# JLC_18V_ESB.net
KiCad netlist of a schematic drawn in Altium Designer
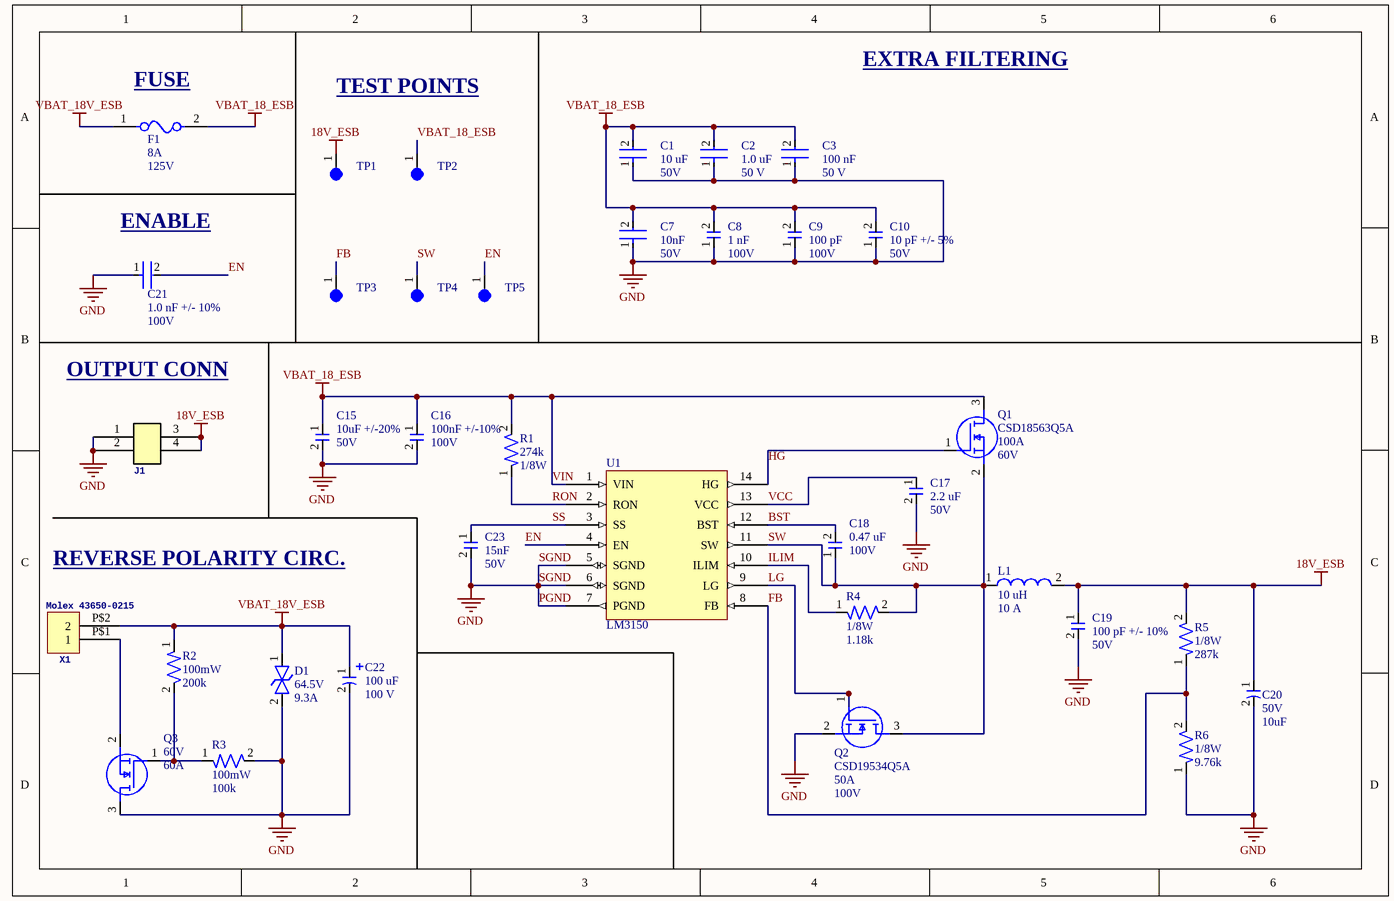
[diagram p0: JLC_18V_ESB.SchDoc]

(export (version "E")
  (design (tool "Eeschema 10.0.6"))
  (components
    (comp (ref "C1")
      (value "CL32B106KBJNNNE")
      (footprint "MasterLib:CAP-1210")
      (description "CAP CER 10UF 50V X7R 1210")
      (fields (field (name "VOLTAGE") "50V") (field (name "CAPACITANCE") "10 uF"))
      (libsource (lib "JLC_25") (part "CAP-10U-0002"))
    )
    (comp (ref "C2")
      (value "CC0805KKX7R9BB105")
      (footprint "MasterLib:CAP-0805")
      (description "CAP CER 1UF 50V X7R 0805")
      (fields (field (name "VOLTAGE") "50 V") (field (name "CAPACITANCE") "1.0 uF"))
      (libsource (lib "JLC_25") (part "CAP-1U-0001"))
    )
    (comp (ref "C3")
      (value "CC0805KRX7R9BB104")
      (footprint "MasterLib:CAP-0805")
      (description "CAP CER 0.1UF 50V X7R 0805")
      (fields (field (name "VOLTAGE RATING") "50 V") (field (name "CAPACITANCE") "100 nF"))
      (libsource (lib "JLC_25") (part "CAP-0.1U-0002"))
    )
    (comp (ref "C7")
      (value "GRM2195C1H103JA01D")
      (footprint "MasterLib:CAP-0805")
      (description "CAP CER 10000PF 50V C0G/NP0 0805")
      (fields (field (name "VOLTAGE") "50V") (field (name "CAPACITANCE") "10nF"))
      (libsource (lib "JLC_25") (part "CAP-10N-0001"))
    )
    (comp (ref "C8")
      (value "CDR01BX102BKUS7185")
      (footprint "CAP-0805")
      (description "1000 pF ±10% 100V Ceramic Capacitor BX 0805 (2012 Metric)")
      (fields (field (name "CAPACITANCE") "1 nF") (field (name "VOLTAGE RATING") "100V"))
      (libsource (lib "MasterLib") (part "CAP-1N-0003"))
    )
    (comp (ref "C9")
      (value "0603N101J101CT")
      (footprint "CAP-0603")
      (description "100 pF ±5% 100V Ceramic Capacitor C0G, NP0 0603 (1608 Metric)")
      (fields
        (field (name "TOLERANCE") "+/-5%")
        (field (name "CAPACITANCE") "100 pF")
        (field (name "VOLTAGE") "100V")
      )
      (libsource (lib "MasterLib") (part "CAP-100P-0002"))
    )
    (comp (ref "C10")
      (value "0603N100J500CT")
      (footprint "CAP-0603")
      (description "10 pF ±5% 50V Ceramic Capacitor C0G, NP0 0603 (1608 Metric)")
      (fields
        (field (name "MANUFACTURER") "Walshin Technology Corporation")
        (field (name "CAPACITANCE") "10 pF +/- 5%")
        (field (name "VOLTAGE RATING") "50V")
      )
      (libsource (lib "MasterLib") (part "CAP-10P-0001"))
    )
    (comp (ref "C15")
      (value "CL31B106KBHNNNE")
      (footprint "CAP-1206")
      (description "10 µF ±10% 50V Ceramic Capacitor X7R 1206 (3216 Metric)")
      (fields
        (field (name "MANUFACTURER") "Samsung Electro-Mechanics")
        (field (name "CAPACITANCE") "10uF +/-20%")
        (field (name "VOLTAGE RATING") "50V")
      )
      (libsource (lib "MasterLib") (part "CAP-10U-0001"))
    )
    (comp (ref "C16")
      (value "CC0603KRX7R0BB104")
      (footprint "CAP-0603")
      (description "CAP CER 0.1UF 100V X7R 0603")
      (fields
        (field (name "MANUFACTURER") "YAGEO")
        (field (name "CAPACITANCE") "100nF +/-10%")
        (field (name "VOLTAGE RATING") "100V")
      )
      (libsource (lib "MasterLib") (part "CAP-100N-0001"))
    )
    (comp (ref "C17")
      (value "UMK107BBJ225KA-T")
      (footprint "CAP-0603")
      (description "2.2 µF ±10% 50V Ceramic Capacitor X5R 0603 (1608 Metric)")
      (fields (field (name "CAPACITANCE") "2.2 uF") (field (name "OLTAGE") "50V"))
      (libsource (lib "MasterLib") (part "CAP-2.2U-0001"))
    )
    (comp (ref "C18")
      (value "KAM21KR72A474KL")
      (footprint "CAP-0805")
      (description "0.47 µF ±10% 100V Ceramic Capacitor X7R 0805 (2012 Metric)")
      (fields
        (field (name "TOLERANCE") "+/- 10%")
        (field (name "CAPACITANCE") "0.47 uF")
        (field (name "VOLTAGE") "100V")
      )
      (libsource (lib "MasterLib") (part "CAP-0.47U-0001"))
    )
    (comp (ref "C19")
      (value "0402B101K500NT")
      (footprint "CAP-0402")
      (description "50V 100pF X7R ±10% 0402 Multilayer Ceramic Capacitors MLCC - SMD/SMT ROHS")
      (fields
        (field (name "JLC PART NUMBER") "C2991538")
        (field (name "CAPACITANCE") "100 pF +/- 10%")
        (field (name "VOLTAGE") "50V")
      )
      (libsource (lib "MasterLib") (part "CAP-100P-0001-JLC"))
    )
    (comp (ref "C20")
      (value "EEE-FK1H100UR")
      (footprint "ELEC-10uF")
      (description "10 µF 50 V Aluminum Electrolytic Capacitors Radial, Can - SMD 2000 Hrs @ 105°C")
      (fields
        (field (name "MANUFACTURER PART NUMBER") "RC0402FR-074K7P")
        (field (name "MANUFACTURER") "YAGEO")
        (field (name "VOLTAGE") "50V")
        (field (name "CAPACITANCE") "10uF")
      )
      (libsource (lib "MasterLib") (part "ELEC-10U-0001"))
    )
    (comp (ref "C21")
      (value "GCM155R72A102KA37D")
      (footprint "CAP-0402")
      (description "100V 1nF X7R ±10% 0402 Multilayer Ceramic Capacitors MLCC - SMD/SMT ROHS")
      (fields (field (name "VOLTAGE") "100V") (field (name "CAPACITANCE") "1.0 nF +/- 10%"))
      (libsource (lib "JLC_18V_ESB-25") (part "CAP-1N-0002"))
    )
    (comp (ref "C22")
      (value "100SEV100M12.5X16")
      (footprint "ELEC-100U-0001")
      (description "100 µF 100 V Aluminum Electrolytic Capacitors Radial, Can - SMD 2000 Hrs @ 85°C")
      (fields
        (field (name "MANUFACTURER") "Rubycon")
        (field (name "TOLERANCE") "+/- 20%")
        (field (name "CAPACITANCE") "100 uF")
        (field (name "VOLTAGE") "100 V")
      )
      (libsource (lib "MasterLib") (part "ELEC-100U-0001"))
    )
    (comp (ref "C23")
      (value "CC0402JRX7R9BB153")
      (footprint "CAP-0402")
      (description "CAP CER 0.015UF 50V X7R 0402")
      (fields (field (name "PARAMETER 1") "15nF") (field (name "PARAMETER 2") "50V"))
      (libsource (lib "MasterLib") (part "CAP-15N-0001"))
    )
    (comp (ref "D1")
      (value "SMBJ40CA")
      (footprint "JLC_25:DO-214AA (SMBJ)")
      (description "TVS DIODE 40VWM 64.5VC DO214AA")
      (fields (field (name "VOLTAGE RATING") "64.5V") (field (name "CURRENT RATING") "9.3A"))
      (libsource (lib "JLC_25") (part "DIO-TVS-0001"))
    )
    (comp (ref "F1")
      (value "01550900M")
      (footprint "JLC_25:FUSE-0001")
      (description "FUSE BLOK CARTRIDGE 125V 10A SMD")
      (fields (field (name "FUSE CURRENT") "8A") (field (name "VOLTAGE RATING") "125V"))
      (libsource (lib "JLC_25") (part "FUSE-0001"))
    )
    (comp (ref "J1")
      (value "Molex 43045-0412")
      (footprint "JLC_25:CONN-4POS-0002")
      (description "CONN HEADER VERT 4POS 3MM")
      (libsource (lib "JLC_25") (part "CONN-4POS-0002"))
    )
    (comp (ref "L1")
      (value "SRP1270-100M")
      (footprint "PWRIND-10U-0002")
      (description "10 µH Shielded Drum Core, Wirewound Inductor 10 A 16.8mOhm Max Nonstandard")
      (fields
        (field (name "TOLERANCE") "+/- 20%")
        (field (name "INDUCTANCE") "10 uH")
        (field (name "DCI") "10 A")
      )
      (libsource (lib "MasterLib") (part "PWRIND-10U-0002"))
    )
    (comp (ref "Q1")
      (value "CSD18563Q5A")
      (footprint "8-VSONP")
      (description "MOSFET N-CH 60V 100A 8VSON")
      (fields
        (field (name "MANUFACTURER PART NUMBER") "T2N7002AK,LM")
        (field (name "MANUFACTURER") "Toshiba")
        (field (name "ID-CONTINUOUS") "100A")
        (field (name "VDS-MAX") "60V")
      )
      (libsource (lib "MasterLib") (part "NMOS-100A-0001"))
    )
    (comp (ref "Q2")
      (value "CSD19534Q5A")
      (footprint "8-VSONP")
      (description "MOSFET N-CH 100V 50A 8VSON")
      (fields
        (field (name "MANUFACTURER PART NUMBER") "T2N7002AK,LM")
        (field (name "MANUFACTURER") "Toshiba")
        (field (name "ID-CONTINUOUS") "50A")
        (field (name "VDS-MAX") "100V")
      )
      (libsource (lib "MasterLib") (part "NMOS-50A-0001"))
    )
    (comp (ref "Q3")
      (value "CSD18543Q3AT")
      (footprint "JLC_25:IC-8VSONCLIP")
      (description "MOSFET N-CH 60V 12A/60A 8VSON")
      (fields (field (name "VOLTAGE") "60V") (field (name "CONTINUOUS CURRENT") "60A"))
      (libsource (lib "JLC_25") (part "NMOS-60A-0001"))
    )
    (comp (ref "R1")
      (value "RC0805FR-07274KL")
      (footprint "RES-0805")
      (description "274 kOhms ±1% 0.125W, 1/8W Chip Resistor 0805 (2012 Metric) Moisture Resistant Thick Film")
      (fields (field (name "RESISTANCE") "274k") (field (name "POWER") "1/8W"))
      (libsource (lib "MasterLib") (part "RES-274k-0001"))
    )
    (comp (ref "R2")
      (value "RC0603FR-07200KL")
      (footprint "MasterLib:RES-0603")
      (description "RES SMD 200K OHM 1% 1/10W 0603")
      (fields
        (field (name "TOLERANCE") "1%")
        (field (name "POWER") "100mW")
        (field (name "RESISTANCE") "200k")
      )
      (libsource (lib "JLC_25") (part "RES-200k-0001"))
    )
    (comp (ref "R3")
      (value "RC0603FR-07100KL")
      (footprint "MasterLib:RES-0603")
      (description "RES SMD 100K OHM 1% 1/10W 0603")
      (fields
        (field (name "TOLERANCE") "1%")
        (field (name "POWER") "100mW")
        (field (name "RESISTANCE") "100k")
      )
      (libsource (lib "JLC_25") (part "RES-100k-0001"))
    )
    (comp (ref "R4")
      (value "RC0805FR-071K18L")
      (footprint "RES-0805")
      (description "1.18 kOhms ±1% 0.125W, 1/8W Chip Resistor 0805 (2012 Metric) Moisture Resistant Thick Film")
      (fields (field (name "POWER") "1/8W") (field (name "RESISTANCE") "1.18k"))
      (libsource (lib "MasterLib") (part "RES-1.18k-0001"))
    )
    (comp (ref "R5")
      (value "RC0805FR-07287KL")
      (footprint "RES-0805")
      (description "287 kOhms ±1% 0.125W, 1/8W Chip Resistor 0805 (2012 Metric) Moisture Resistant Thick Film")
      (fields (field (name "POWER") "1/8W") (field (name "RESISTANCE") "287k"))
      (libsource (lib "MasterLib") (part "RES-287k-0001"))
    )
    (comp (ref "R6")
      (value "RC0805FR-079K76L")
      (footprint "RES-0805")
      (description "9.76 kOhms ±1% 0.125W, 1/8W Chip Resistor 0805 (2012 Metric) Moisture Resistant Thick Film")
      (fields (field (name "POWER") "1/8W") (field (name "RESISTANCE") "9.76k"))
      (libsource (lib "MasterLib") (part "RES-9.76k-0001"))
    )
    (comp (ref "TP1")
      (value "5003")
      (footprint "TEST-POINT-0001")
      (description "Oranange PC Test Point, Miniature Phoisphor Bronze Silver Plating Through Hole Mounting Type")
      (libsource (lib "*") (part "TEST-POINT-0001"))
    )
    (comp (ref "TP2")
      (value "5003")
      (footprint "TEST-POINT-0001")
      (description "Oranange PC Test Point, Miniature Phoisphor Bronze Silver Plating Through Hole Mounting Type")
      (libsource (lib "*") (part "TEST-POINT-0001"))
    )
    (comp (ref "TP3")
      (value "5003")
      (footprint "TEST-POINT-0001")
      (description "Oranange PC Test Point, Miniature Phoisphor Bronze Silver Plating Through Hole Mounting Type")
      (libsource (lib "*") (part "TEST-POINT-0001"))
    )
    (comp (ref "TP4")
      (value "5003")
      (footprint "TEST-POINT-0001")
      (description "Oranange PC Test Point, Miniature Phoisphor Bronze Silver Plating Through Hole Mounting Type")
      (libsource (lib "*") (part "TEST-POINT-0001"))
    )
    (comp (ref "TP5")
      (value "5003")
      (footprint "TEST-POINT-0001")
      (description "Oranange PC Test Point, Miniature Phoisphor Bronze Silver Plating Through Hole Mounting Type")
      (libsource (lib "*") (part "TEST-POINT-0001"))
    )
    (comp (ref "U1")
      (value "LM3150")
      (footprint "IC-14HTSSOP")
      (description "Buck Regulator Positive Output Step-Down DC-DC Controller IC 14-HTSSOP")
      (libsource (lib "MasterLib") (part "IC-ESB-0001"))
    )
    (comp (ref "X1")
      (value "Molex 43650-0215")
      (footprint "43650-0215")
      (libsource (lib "Molex Microfit") (part "Micro-Fit Molex 2 Pin Vertical"))
    )
  )
  (nets
    (net (code "1") (name "/BST") (class "Default")
      (node (ref "C18") (pin "2") (pinfunction "2_2") (pintype "passive"))
      (node (ref "U1") (pin "12") (pinfunction "BST_12") (pintype "input"))
    )
    (net (code "2") (name "/EN") (class "Default")
      (node (ref "C21") (pin "2") (pinfunction "2_2") (pintype "passive"))
      (node (ref "TP5") (pin "1") (pinfunction "0_1") (pintype "passive"))
      (node (ref "U1") (pin "4") (pinfunction "EN_4") (pintype "input"))
    )
    (net (code "3") (name "/FB") (class "Default")
      (node (ref "R5") (pin "1") (pinfunction "1_1") (pintype "passive"))
      (node (ref "R6") (pin "2") (pinfunction "2_2") (pintype "passive"))
      (node (ref "TP3") (pin "1") (pinfunction "0_1") (pintype "passive"))
      (node (ref "U1") (pin "8") (pinfunction "FB_8") (pintype "input"))
    )
    (net (code "4") (name "/HG") (class "Default")
      (node (ref "Q1") (pin "1") (pinfunction "G_1") (pintype "passive"))
      (node (ref "U1") (pin "14") (pinfunction "HG_14") (pintype "output"))
    )
    (net (code "5") (name "/ILIM") (class "Default")
      (node (ref "R4") (pin "1") (pinfunction "1_1") (pintype "passive"))
      (node (ref "U1") (pin "10") (pinfunction "ILIM_10") (pintype "input"))
    )
    (net (code "6") (name "/LG") (class "Default")
      (node (ref "Q2") (pin "1") (pinfunction "G_1") (pintype "passive"))
      (node (ref "U1") (pin "9") (pinfunction "LG_9") (pintype "output"))
    )
    (net (code "7") (name "/RON") (class "Default")
      (node (ref "R1") (pin "1") (pinfunction "1_1") (pintype "passive"))
      (node (ref "U1") (pin "2") (pinfunction "RON_2") (pintype "input"))
    )
    (net (code "8") (name "/SS") (class "Default")
      (node (ref "C23") (pin "1") (pinfunction "1_1") (pintype "passive"))
      (node (ref "U1") (pin "3") (pinfunction "SS_3") (pintype "input"))
    )
    (net (code "9") (name "/SW") (class "Default")
      (node (ref "C18") (pin "1") (pinfunction "1_1") (pintype "passive"))
      (node (ref "L1") (pin "1") (pinfunction "1_1") (pintype "passive"))
      (node (ref "Q1") (pin "2") (pinfunction "S_2") (pintype "passive"))
      (node (ref "Q2") (pin "3") (pinfunction "D_3") (pintype "passive"))
      (node (ref "R4") (pin "2") (pinfunction "2_2") (pintype "passive"))
      (node (ref "TP4") (pin "1") (pinfunction "0_1") (pintype "passive"))
      (node (ref "U1") (pin "11") (pinfunction "SW_11") (pintype "output"))
    )
    (net (code "10") (name "/VCC") (class "Default")
      (node (ref "C17") (pin "1") (pinfunction "1_1") (pintype "passive"))
      (node (ref "U1") (pin "13") (pinfunction "VCC_13") (pintype "output"))
    )
    (net (code "11") (name "18V_ESB") (class "Default")
      (node (ref "C19") (pin "1") (pinfunction "1_1") (pintype "passive"))
      (node (ref "C20") (pin "1") (pinfunction "1_1") (pintype "passive"))
      (node (ref "J1") (pin "3") (pinfunction "3_3") (pintype "passive"))
      (node (ref "J1") (pin "4") (pinfunction "4_4") (pintype "passive"))
      (node (ref "L1") (pin "2") (pinfunction "2_2") (pintype "passive"))
      (node (ref "R5") (pin "2") (pinfunction "2_2") (pintype "passive"))
      (node (ref "TP1") (pin "1") (pinfunction "0_1") (pintype "passive"))
    )
    (net (code "12") (name "GND") (class "Default")
      (node (ref "C1") (pin "1") (pinfunction "1_1") (pintype "passive"))
      (node (ref "C10") (pin "1") (pinfunction "1_1") (pintype "passive"))
      (node (ref "C15") (pin "2") (pinfunction "2_2") (pintype "passive"))
      (node (ref "C16") (pin "2") (pinfunction "2_2") (pintype "passive"))
      (node (ref "C17") (pin "2") (pinfunction "2_2") (pintype "passive"))
      (node (ref "C19") (pin "2") (pinfunction "2_2") (pintype "passive"))
      (node (ref "C2") (pin "1") (pinfunction "1_1") (pintype "passive"))
      (node (ref "C20") (pin "2") (pinfunction "2_2") (pintype "passive"))
      (node (ref "C21") (pin "1") (pinfunction "1_1") (pintype "passive"))
      (node (ref "C22") (pin "2") (pinfunction "2_2") (pintype "passive"))
      (node (ref "C23") (pin "2") (pinfunction "2_2") (pintype "passive"))
      (node (ref "C3") (pin "1") (pinfunction "1_1") (pintype "passive"))
      (node (ref "C7") (pin "1") (pinfunction "1_1") (pintype "passive"))
      (node (ref "C8") (pin "1") (pinfunction "1_1") (pintype "passive"))
      (node (ref "C9") (pin "1") (pinfunction "1_1") (pintype "passive"))
      (node (ref "D1") (pin "2") (pintype "passive"))
      (node (ref "J1") (pin "1") (pinfunction "1_1") (pintype "passive"))
      (node (ref "J1") (pin "2") (pinfunction "2_2") (pintype "passive"))
      (node (ref "Q2") (pin "2") (pinfunction "S_2") (pintype "passive"))
      (node (ref "Q3") (pin "3") (pinfunction "D_3") (pintype "passive"))
      (node (ref "R3") (pin "2") (pinfunction "2_2") (pintype "passive"))
      (node (ref "R6") (pin "1") (pinfunction "1_1") (pintype "passive"))
      (node (ref "U1") (pin "5") (pinfunction "SGND_5") (pintype "bidirectional"))
      (node (ref "U1") (pin "6") (pinfunction "SGND_6") (pintype "bidirectional"))
      (node (ref "U1") (pin "7") (pinfunction "PGND_7") (pintype "output"))
    )
    (net (code "13") (name "Net-(Q3-G)") (class "Default")
      (node (ref "Q3") (pin "1") (pinfunction "G_1") (pintype "passive"))
      (node (ref "R2") (pin "2") (pinfunction "2_2") (pintype "passive"))
      (node (ref "R3") (pin "1") (pinfunction "1_1") (pintype "passive"))
    )
    (net (code "14") (name "Net-(Q3-S)") (class "Default")
      (node (ref "Q3") (pin "2") (pinfunction "S_2") (pintype "passive"))
      (node (ref "X1") (pin "P$1") (pinfunction "1_P$1") (pintype "passive"))
    )
    (net (code "15") (name "VBAT_18V_ESB") (class "Default")
      (node (ref "C22") (pin "1") (pinfunction "1_1") (pintype "passive"))
      (node (ref "D1") (pin "1") (pintype "passive"))
      (node (ref "F1") (pin "1") (pinfunction "1_1") (pintype "passive"))
      (node (ref "R2") (pin "1") (pinfunction "1_1") (pintype "passive"))
      (node (ref "X1") (pin "P$2") (pinfunction "2_P$2") (pintype "passive"))
    )
    (net (code "16") (name "VBAT_18_ESB") (class "Default")
      (node (ref "C1") (pin "2") (pinfunction "2_2") (pintype "passive"))
      (node (ref "C10") (pin "2") (pinfunction "2_2") (pintype "passive"))
      (node (ref "C15") (pin "1") (pinfunction "1_1") (pintype "passive"))
      (node (ref "C16") (pin "1") (pinfunction "1_1") (pintype "passive"))
      (node (ref "C2") (pin "2") (pinfunction "2_2") (pintype "passive"))
      (node (ref "C3") (pin "2") (pinfunction "2_2") (pintype "passive"))
      (node (ref "C7") (pin "2") (pinfunction "2_2") (pintype "passive"))
      (node (ref "C8") (pin "2") (pinfunction "2_2") (pintype "passive"))
      (node (ref "C9") (pin "2") (pinfunction "2_2") (pintype "passive"))
      (node (ref "F1") (pin "2") (pinfunction "2_2") (pintype "passive"))
      (node (ref "Q1") (pin "3") (pinfunction "D_3") (pintype "passive"))
      (node (ref "R1") (pin "2") (pinfunction "2_2") (pintype "passive"))
      (node (ref "TP2") (pin "1") (pinfunction "0_1") (pintype "passive"))
      (node (ref "U1") (pin "1") (pinfunction "VIN_1") (pintype "input"))
    )
  )
)
